# NRF24l01.net
KiCad netlist of a schematic drawn in Altium Designer
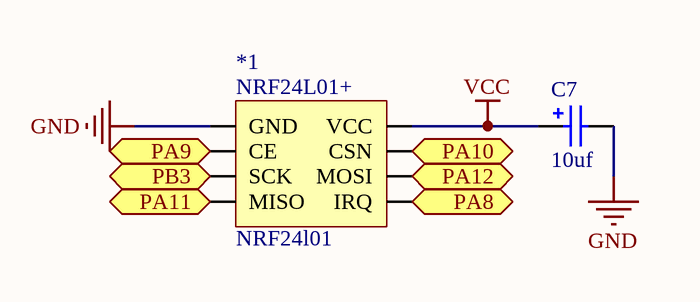
[diagram p0: NRF24l01.SchDoc]

(export (version "E")
  (design (tool "Eeschema 10.0.6"))
  (components
    (comp (ref "*1") (value "NRF24l01") (footprint "NRF24l01") (libsource (lib "Tesis") (part "NRF24l01")))
    (comp (ref "C7")
      (value "10uf")
      (footprint "SMD-0805C")
      (description "Aluminum Electrolytic Capacitor, Radial Style with Long Leads: 47uF, 35V")
      (fields (field (name "PUBLISHER") "Altium Limited"))
      (libsource (lib "Tesis") (part "EKA00AA247F00"))
    )
  )
  (nets
    (net (code "1") (name "/PA8") (class "Default")
      (node (ref "*1") (pin "8") (pinfunction "IRQ_8") (pintype "passive"))
    )
    (net (code "2") (name "/PA9") (class "Default")
      (node (ref "*1") (pin "3") (pinfunction "CE_3") (pintype "passive"))
    )
    (net (code "3") (name "/PA10") (class "Default")
      (node (ref "*1") (pin "4") (pinfunction "CSN_4") (pintype "passive"))
    )
    (net (code "4") (name "/PA11") (class "Default")
      (node (ref "*1") (pin "7") (pinfunction "MISO_7") (pintype "passive"))
    )
    (net (code "5") (name "/PA12") (class "Default")
      (node (ref "*1") (pin "6") (pinfunction "MOSI_6") (pintype "passive"))
    )
    (net (code "6") (name "/PB3") (class "Default")
      (node (ref "*1") (pin "5") (pinfunction "SCK_5") (pintype "passive"))
    )
    (net (code "7") (name "GND") (class "Default")
      (node (ref "*1") (pin "1") (pinfunction "GND_1") (pintype "passive"))
      (node (ref "C7") (pin "2") (pinfunction "2_2") (pintype "passive"))
    )
    (net (code "8") (name "VCC") (class "Default")
      (node (ref "*1") (pin "2") (pinfunction "VCC_2") (pintype "passive"))
      (node (ref "C7") (pin "1") (pinfunction "1_1") (pintype "passive"))
    )
  )
)
